# LB-BIT-w2_BRANCH-v03_3_3.net
KiCad netlist of a schematic drawn in EAGLE
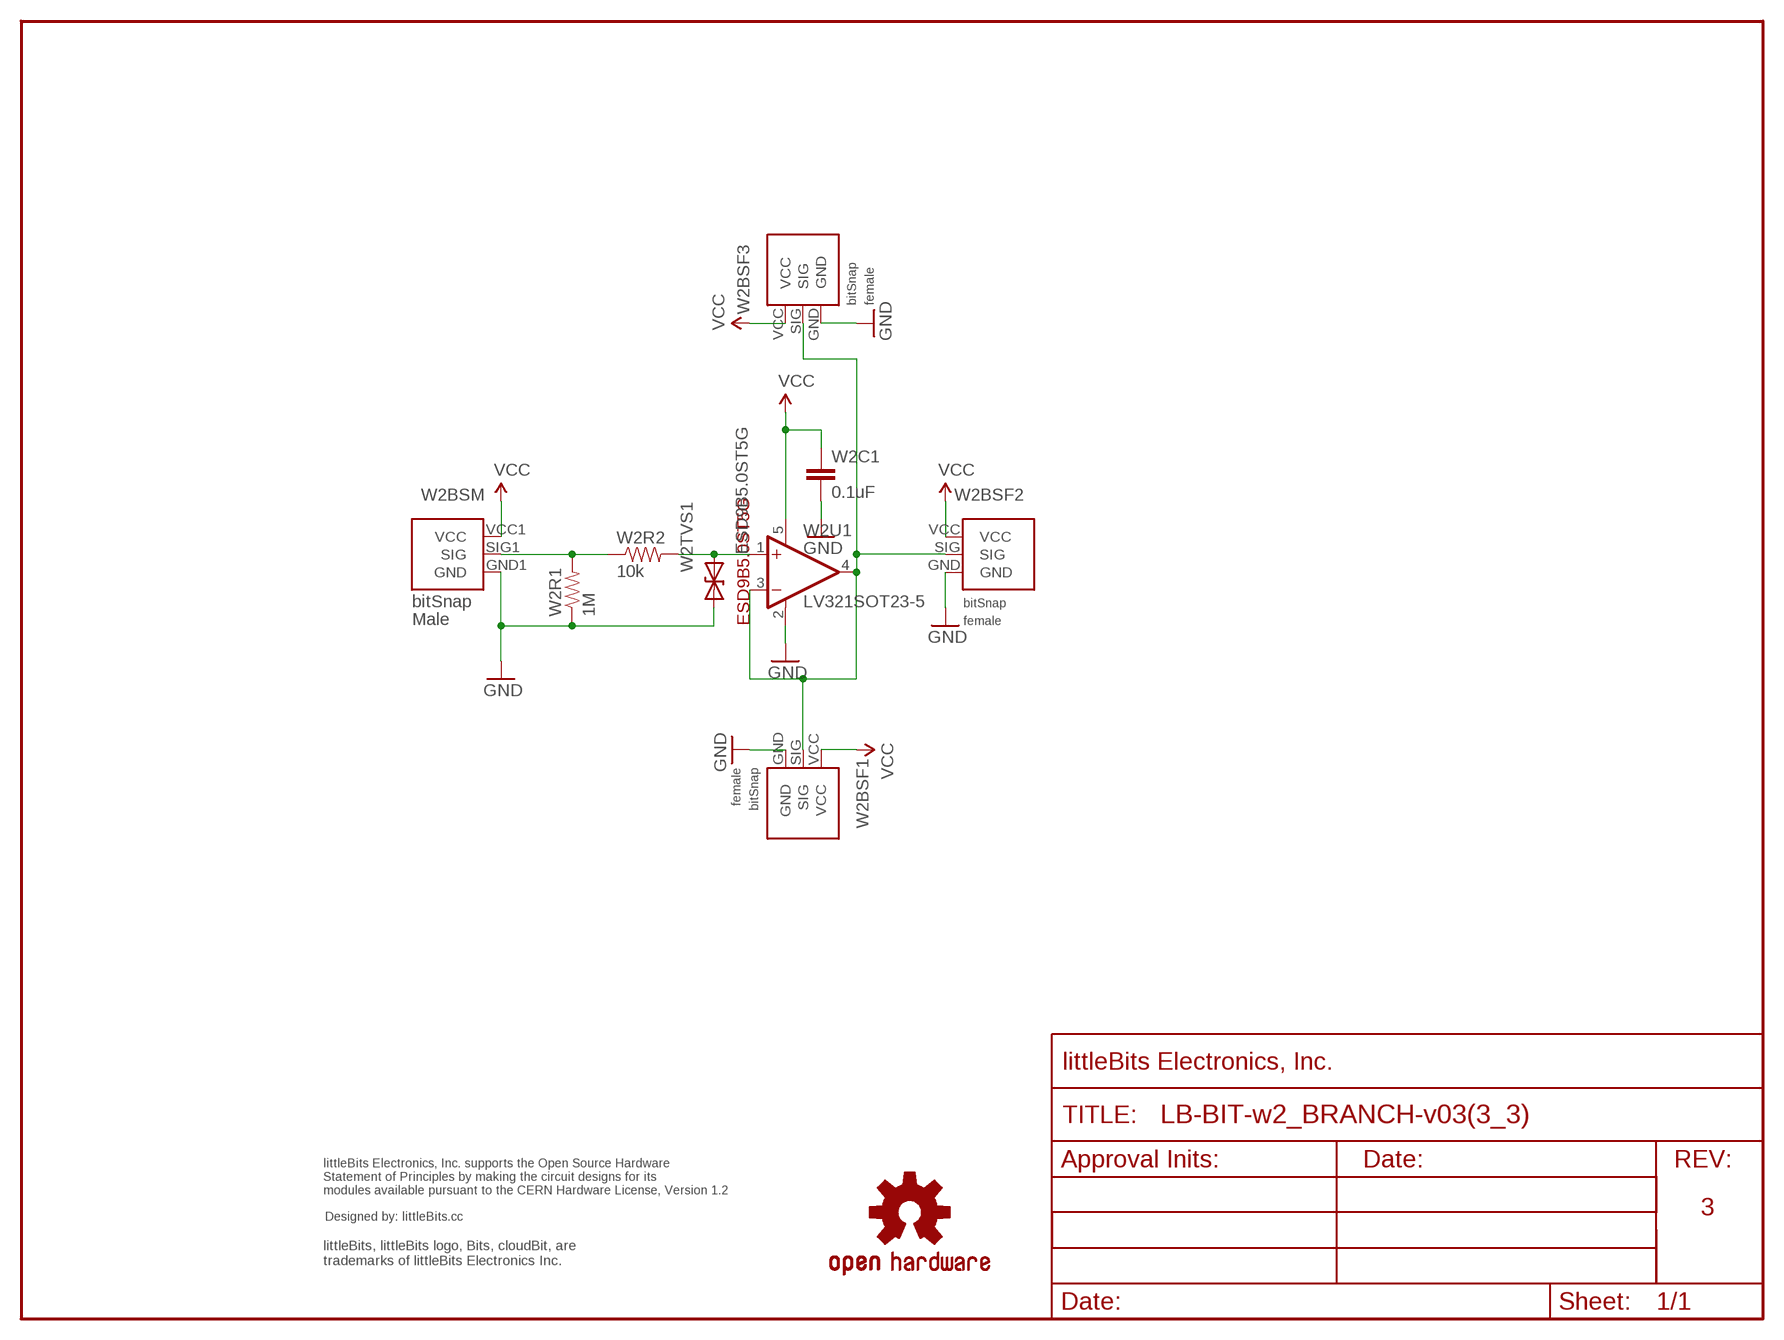
[diagram p0: schematic, sheet 1]

(export (version "E")
  (design (tool "Eeschema 10.0.6"))
  (components
    (comp (ref "U$1")
      (value "OSHWCREDIT")
      (footprint "eagle-import:OSHWCREDIT")
      (libsource (lib "eagle-import") (part "OSHWCREDIT"))
    )
    (comp (ref "U$2")
      (value "FRAME-LETTER-OHWOHW")
      (footprint "eagle-import:FABDWG01-OHW")
      (libsource (lib "eagle-import") (part "FRAME-LETTER-OHWOHW"))
    )
    (comp (ref "U$6")
      (value "OSHW-LOGOL")
      (footprint "eagle-import:OSHW-LOGO-L")
      (libsource (lib "eagle-import") (part "OSHW-LOGOL"))
    )
    (comp (ref "W2BSF1")
      (value "BITSNAP_V03_FEMALE")
      (footprint "eagle-import:BITSNAP_V03_FEMALE")
      (libsource (lib "eagle-import") (part "BITSNAP_V03_FEMALE"))
    )
    (comp (ref "W2BSF2")
      (value "BITSNAP_V03_FEMALE")
      (footprint "eagle-import:BITSNAP_V03_FEMALE")
      (libsource (lib "eagle-import") (part "BITSNAP_V03_FEMALE"))
    )
    (comp (ref "W2BSF3")
      (value "BITSNAP_V03_FEMALE")
      (footprint "eagle-import:BITSNAP_V03_FEMALE")
      (libsource (lib "eagle-import") (part "BITSNAP_V03_FEMALE"))
    )
    (comp (ref "W2BSM")
      (value "BITSNAP_V03_MALE")
      (footprint "eagle-import:BITSNAP_V03_MALE")
      (libsource (lib "eagle-import") (part "BITSNAP_V03_MALE"))
    )
    (comp (ref "W2C1")
      (value "0.1uF")
      (footprint "eagle-import:CAP-0603")
      (libsource (lib "eagle-import") (part "CAPCAP-0603"))
    )
    (comp (ref "W2R1")
      (value "1M")
      (footprint "eagle-import:RES-0603")
      (libsource (lib "eagle-import") (part "RESISTOR0603"))
    )
    (comp (ref "W2R2")
      (value "10k")
      (footprint "eagle-import:RES-0603")
      (libsource (lib "eagle-import") (part "RESISTOR0603"))
    )
    (comp (ref "W2TVS1")
      (value "ESD9B5.0ST5G")
      (footprint "eagle-import:SOD-923")
      (libsource (lib "eagle-import") (part "DIODE-TVSSOD-923"))
    )
    (comp (ref "W2U1")
      (value "LV321SOT23-5")
      (footprint "eagle-import:SOT23-5")
      (libsource (lib "eagle-import") (part "LV321SOT23-5"))
    )
  )
  (nets
    (net (code "1") (name "GND") (class "Default")
      (node (ref "W2BSF1") (pin "GND") (pinfunction "GND_GND") (pintype "bidirectional"))
      (node (ref "W2BSF2") (pin "GND") (pinfunction "GND_GND") (pintype "bidirectional"))
      (node (ref "W2BSF3") (pin "GND") (pinfunction "GND_GND") (pintype "bidirectional"))
      (node (ref "W2BSM") (pin "GND1") (pinfunction "GND_GND1") (pintype "bidirectional"))
      (node (ref "W2C1") (pin "2") (pinfunction "2_2") (pintype "passive"))
      (node (ref "W2R1") (pin "1") (pinfunction "1_1") (pintype "passive"))
      (node (ref "W2TVS1") (pin "1") (pinfunction "A_1") (pintype "passive"))
      (node (ref "W2U1") (pin "2") (pinfunction "V-_2") (pintype "power_in"))
    )
    (net (code "2") (name "Net-(W2BSM-SIG)") (class "Default")
      (node (ref "W2BSM") (pin "SIG1") (pinfunction "SIG_SIG1") (pintype "bidirectional"))
      (node (ref "W2R1") (pin "2") (pinfunction "2_2") (pintype "passive"))
      (node (ref "W2R2") (pin "1") (pinfunction "1_1") (pintype "passive"))
    )
    (net (code "3") (name "Net-(W2TVS1-C)") (class "Default")
      (node (ref "W2R2") (pin "2") (pinfunction "2_2") (pintype "passive"))
      (node (ref "W2TVS1") (pin "2") (pinfunction "C_2") (pintype "passive"))
      (node (ref "W2U1") (pin "1") (pinfunction "+IN_1") (pintype "input"))
    )
    (net (code "4") (name "Net-(W2U1--IN)") (class "Default")
      (node (ref "W2BSF1") (pin "SIG") (pinfunction "SIG_SIG") (pintype "bidirectional"))
      (node (ref "W2BSF2") (pin "SIG") (pinfunction "SIG_SIG") (pintype "bidirectional"))
      (node (ref "W2BSF3") (pin "SIG") (pinfunction "SIG_SIG") (pintype "bidirectional"))
      (node (ref "W2U1") (pin "3") (pinfunction "-IN_3") (pintype "input"))
      (node (ref "W2U1") (pin "4") (pinfunction "OUT_4") (pintype "output"))
    )
    (net (code "5") (name "VCC") (class "Default")
      (node (ref "W2BSF1") (pin "VCC") (pinfunction "VCC_VCC") (pintype "bidirectional"))
      (node (ref "W2BSF2") (pin "VCC") (pinfunction "VCC_VCC") (pintype "bidirectional"))
      (node (ref "W2BSF3") (pin "VCC") (pinfunction "VCC_VCC") (pintype "bidirectional"))
      (node (ref "W2BSM") (pin "VCC1") (pinfunction "VCC_VCC1") (pintype "bidirectional"))
      (node (ref "W2C1") (pin "1") (pinfunction "1_1") (pintype "passive"))
      (node (ref "W2U1") (pin "5") (pinfunction "V+_5") (pintype "power_in"))
    )
  )
)
